# con-right-bot.net
KiCad netlist of a schematic drawn in Altium Designer
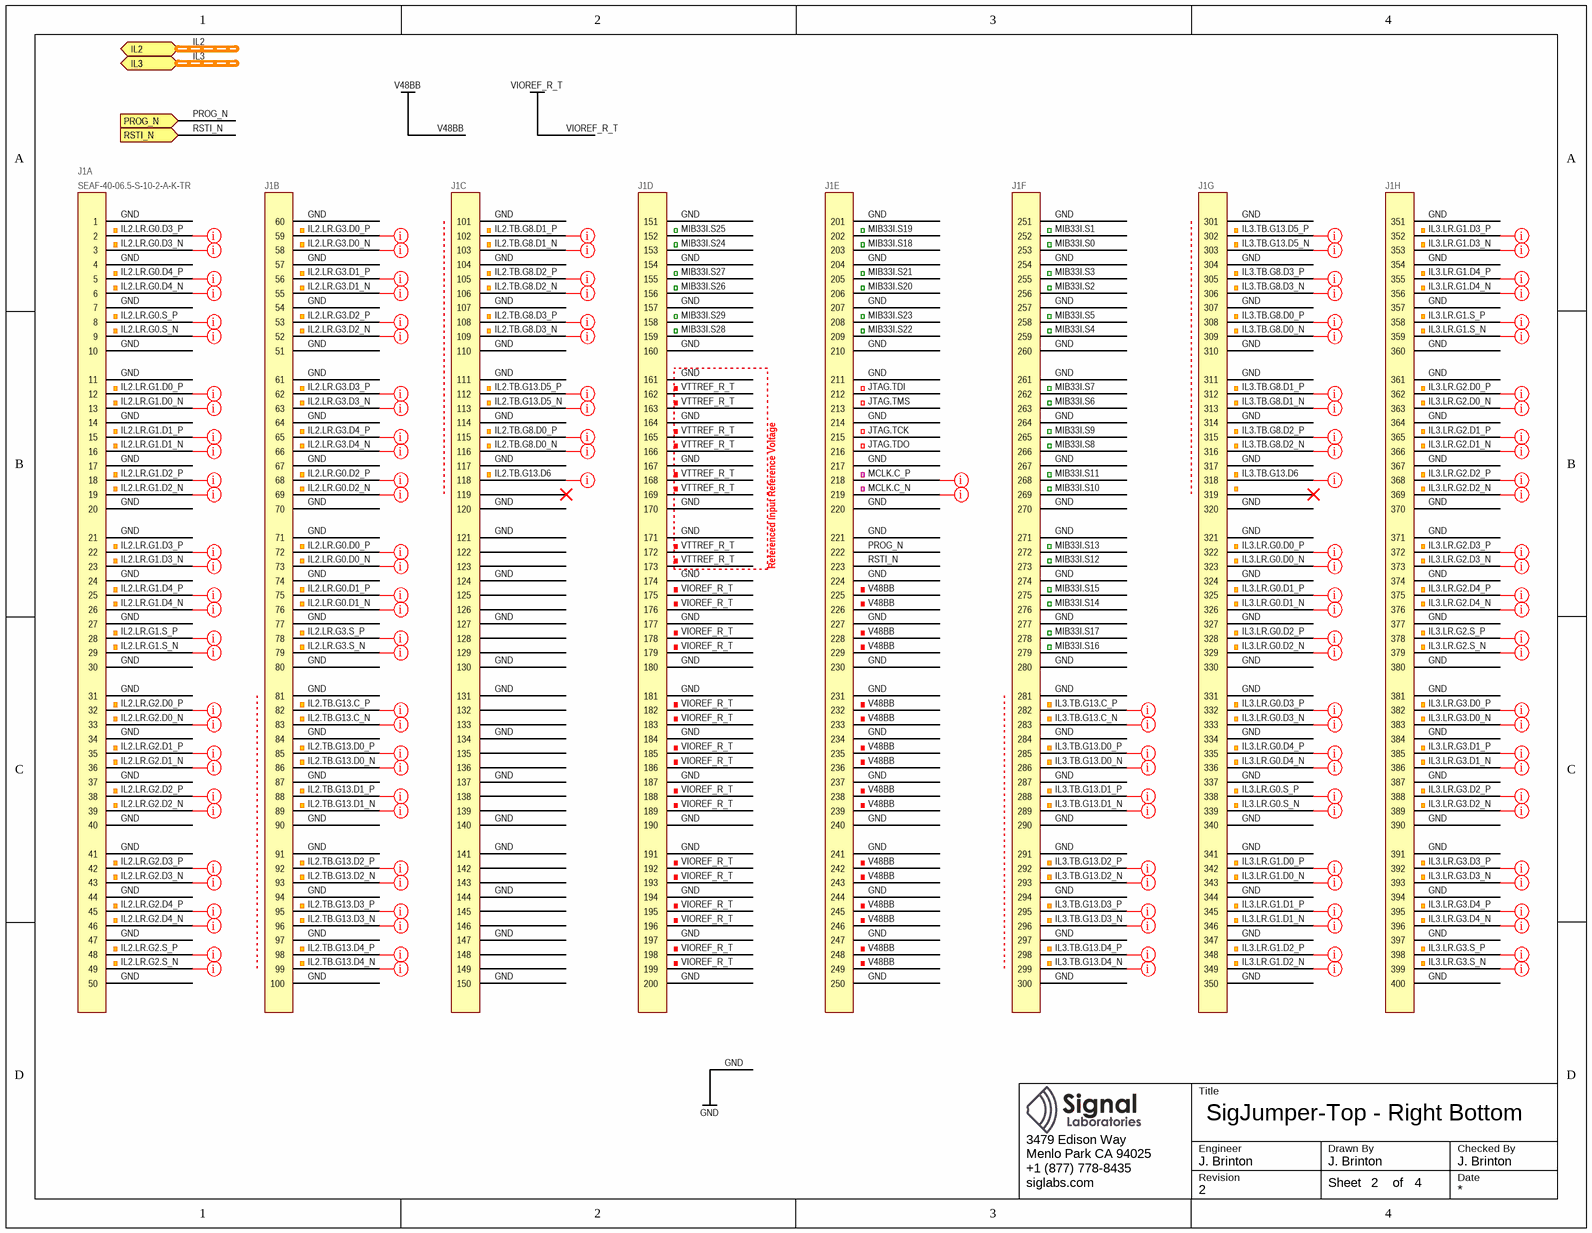
[diagram p0: con-right-bot.SchDoc]

(export (version "E")
  (design (tool "Eeschema 10.0.6"))
  (components
    (comp (ref "J1")
      (value "SEAF-40-06.5-S-10-2-A-K-TR")
      (footprint "samtec:SEAF-40-06.5-S-10-2-A-K-TR")
      (description "Terminal Array Assembly, Surface Mount, 0.050\" Pitch, 400 Pins")
      (fields (field (name "MANUFACTURER") "Samtec"))
      (libsource (lib "samtec") (part "SEAF-40-06.5-S-10-2-A-K-TR"))
    )
  )
  (nets
    (net (code "3") (name "/IL2.LR.G0.D0_N") (class "Default")
      (node (ref "J1") (pin "73") (pinfunction "73_73") (pintype "passive"))
    )
    (net (code "4") (name "/IL2.LR.G0.D0_P") (class "Default")
      (node (ref "J1") (pin "72") (pinfunction "72_72") (pintype "passive"))
    )
    (net (code "5") (name "/IL2.LR.G0.D1_N") (class "Default")
      (node (ref "J1") (pin "76") (pinfunction "76_76") (pintype "passive"))
    )
    (net (code "6") (name "/IL2.LR.G0.D1_P") (class "Default")
      (node (ref "J1") (pin "75") (pinfunction "75_75") (pintype "passive"))
    )
    (net (code "7") (name "/IL2.LR.G0.D2_N") (class "Default")
      (node (ref "J1") (pin "69") (pinfunction "69_69") (pintype "passive"))
    )
    (net (code "8") (name "/IL2.LR.G0.D2_P") (class "Default")
      (node (ref "J1") (pin "68") (pinfunction "68_68") (pintype "passive"))
    )
    (net (code "9") (name "/IL2.LR.G0.D3_N") (class "Default")
      (node (ref "J1") (pin "3") (pinfunction "3_3") (pintype "passive"))
    )
    (net (code "10") (name "/IL2.LR.G0.D3_P") (class "Default")
      (node (ref "J1") (pin "2") (pinfunction "2_2") (pintype "passive"))
    )
    (net (code "11") (name "/IL2.LR.G0.D4_N") (class "Default")
      (node (ref "J1") (pin "6") (pinfunction "6_6") (pintype "passive"))
    )
    (net (code "12") (name "/IL2.LR.G0.D4_P") (class "Default")
      (node (ref "J1") (pin "5") (pinfunction "5_5") (pintype "passive"))
    )
    (net (code "13") (name "/IL2.LR.G0.S_N") (class "Default")
      (node (ref "J1") (pin "9") (pinfunction "9_9") (pintype "passive"))
    )
    (net (code "14") (name "/IL2.LR.G0.S_P") (class "Default")
      (node (ref "J1") (pin "8") (pinfunction "8_8") (pintype "passive"))
    )
    (net (code "15") (name "/IL2.LR.G1.D0_N") (class "Default")
      (node (ref "J1") (pin "13") (pinfunction "13_13") (pintype "passive"))
    )
    (net (code "16") (name "/IL2.LR.G1.D0_P") (class "Default")
      (node (ref "J1") (pin "12") (pinfunction "12_12") (pintype "passive"))
    )
    (net (code "17") (name "/IL2.LR.G1.D1_N") (class "Default")
      (node (ref "J1") (pin "16") (pinfunction "16_16") (pintype "passive"))
    )
    (net (code "18") (name "/IL2.LR.G1.D1_P") (class "Default")
      (node (ref "J1") (pin "15") (pinfunction "15_15") (pintype "passive"))
    )
    (net (code "19") (name "/IL2.LR.G1.D2_N") (class "Default")
      (node (ref "J1") (pin "19") (pinfunction "19_19") (pintype "passive"))
    )
    (net (code "20") (name "/IL2.LR.G1.D2_P") (class "Default")
      (node (ref "J1") (pin "18") (pinfunction "18_18") (pintype "passive"))
    )
    (net (code "21") (name "/IL2.LR.G1.D3_N") (class "Default")
      (node (ref "J1") (pin "23") (pinfunction "23_23") (pintype "passive"))
    )
    (net (code "22") (name "/IL2.LR.G1.D3_P") (class "Default")
      (node (ref "J1") (pin "22") (pinfunction "22_22") (pintype "passive"))
    )
    (net (code "23") (name "/IL2.LR.G1.D4_N") (class "Default")
      (node (ref "J1") (pin "26") (pinfunction "26_26") (pintype "passive"))
    )
    (net (code "24") (name "/IL2.LR.G1.D4_P") (class "Default")
      (node (ref "J1") (pin "25") (pinfunction "25_25") (pintype "passive"))
    )
    (net (code "25") (name "/IL2.LR.G1.S_N") (class "Default")
      (node (ref "J1") (pin "29") (pinfunction "29_29") (pintype "passive"))
    )
    (net (code "26") (name "/IL2.LR.G1.S_P") (class "Default")
      (node (ref "J1") (pin "28") (pinfunction "28_28") (pintype "passive"))
    )
    (net (code "27") (name "/IL2.LR.G2.D0_N") (class "Default")
      (node (ref "J1") (pin "33") (pinfunction "33_33") (pintype "passive"))
    )
    (net (code "28") (name "/IL2.LR.G2.D0_P") (class "Default")
      (node (ref "J1") (pin "32") (pinfunction "32_32") (pintype "passive"))
    )
    (net (code "29") (name "/IL2.LR.G2.D1_N") (class "Default")
      (node (ref "J1") (pin "36") (pinfunction "36_36") (pintype "passive"))
    )
    (net (code "30") (name "/IL2.LR.G2.D1_P") (class "Default")
      (node (ref "J1") (pin "35") (pinfunction "35_35") (pintype "passive"))
    )
    (net (code "31") (name "/IL2.LR.G2.D2_N") (class "Default")
      (node (ref "J1") (pin "39") (pinfunction "39_39") (pintype "passive"))
    )
    (net (code "32") (name "/IL2.LR.G2.D2_P") (class "Default")
      (node (ref "J1") (pin "38") (pinfunction "38_38") (pintype "passive"))
    )
    (net (code "33") (name "/IL2.LR.G2.D3_N") (class "Default")
      (node (ref "J1") (pin "43") (pinfunction "43_43") (pintype "passive"))
    )
    (net (code "34") (name "/IL2.LR.G2.D3_P") (class "Default")
      (node (ref "J1") (pin "42") (pinfunction "42_42") (pintype "passive"))
    )
    (net (code "35") (name "/IL2.LR.G2.D4_N") (class "Default")
      (node (ref "J1") (pin "46") (pinfunction "46_46") (pintype "passive"))
    )
    (net (code "36") (name "/IL2.LR.G2.D4_P") (class "Default")
      (node (ref "J1") (pin "45") (pinfunction "45_45") (pintype "passive"))
    )
    (net (code "37") (name "/IL2.LR.G2.S_N") (class "Default")
      (node (ref "J1") (pin "49") (pinfunction "49_49") (pintype "passive"))
    )
    (net (code "38") (name "/IL2.LR.G2.S_P") (class "Default")
      (node (ref "J1") (pin "48") (pinfunction "48_48") (pintype "passive"))
    )
    (net (code "39") (name "/IL2.LR.G3.D0_N") (class "Default")
      (node (ref "J1") (pin "58") (pinfunction "58_58") (pintype "passive"))
    )
    (net (code "40") (name "/IL2.LR.G3.D0_P") (class "Default")
      (node (ref "J1") (pin "59") (pinfunction "59_59") (pintype "passive"))
    )
    (net (code "41") (name "/IL2.LR.G3.D1_N") (class "Default")
      (node (ref "J1") (pin "55") (pinfunction "55_55") (pintype "passive"))
    )
    (net (code "42") (name "/IL2.LR.G3.D1_P") (class "Default")
      (node (ref "J1") (pin "56") (pinfunction "56_56") (pintype "passive"))
    )
    (net (code "43") (name "/IL2.LR.G3.D2_N") (class "Default")
      (node (ref "J1") (pin "52") (pinfunction "52_52") (pintype "passive"))
    )
    (net (code "44") (name "/IL2.LR.G3.D2_P") (class "Default")
      (node (ref "J1") (pin "53") (pinfunction "53_53") (pintype "passive"))
    )
    (net (code "45") (name "/IL2.LR.G3.D3_N") (class "Default")
      (node (ref "J1") (pin "63") (pinfunction "63_63") (pintype "passive"))
    )
    (net (code "46") (name "/IL2.LR.G3.D3_P") (class "Default")
      (node (ref "J1") (pin "62") (pinfunction "62_62") (pintype "passive"))
    )
    (net (code "47") (name "/IL2.LR.G3.D4_N") (class "Default")
      (node (ref "J1") (pin "66") (pinfunction "66_66") (pintype "passive"))
    )
    (net (code "48") (name "/IL2.LR.G3.D4_P") (class "Default")
      (node (ref "J1") (pin "65") (pinfunction "65_65") (pintype "passive"))
    )
    (net (code "49") (name "/IL2.LR.G3.S_N") (class "Default")
      (node (ref "J1") (pin "79") (pinfunction "79_79") (pintype "passive"))
    )
    (net (code "50") (name "/IL2.LR.G3.S_P") (class "Default")
      (node (ref "J1") (pin "78") (pinfunction "78_78") (pintype "passive"))
    )
    (net (code "51") (name "/IL2.TB.G8.D0_N") (class "Default")
      (node (ref "J1") (pin "116") (pinfunction "116_116") (pintype "passive"))
    )
    (net (code "52") (name "/IL2.TB.G8.D0_P") (class "Default")
      (node (ref "J1") (pin "115") (pinfunction "115_115") (pintype "passive"))
    )
    (net (code "53") (name "/IL2.TB.G8.D1_N") (class "Default")
      (node (ref "J1") (pin "103") (pinfunction "103_103") (pintype "passive"))
    )
    (net (code "54") (name "/IL2.TB.G8.D1_P") (class "Default")
      (node (ref "J1") (pin "102") (pinfunction "102_102") (pintype "passive"))
    )
    (net (code "55") (name "/IL2.TB.G8.D2_N") (class "Default")
      (node (ref "J1") (pin "106") (pinfunction "106_106") (pintype "passive"))
    )
    (net (code "56") (name "/IL2.TB.G8.D2_P") (class "Default")
      (node (ref "J1") (pin "105") (pinfunction "105_105") (pintype "passive"))
    )
    (net (code "57") (name "/IL2.TB.G8.D3_N") (class "Default")
      (node (ref "J1") (pin "109") (pinfunction "109_109") (pintype "passive"))
    )
    (net (code "58") (name "/IL2.TB.G8.D3_P") (class "Default")
      (node (ref "J1") (pin "108") (pinfunction "108_108") (pintype "passive"))
    )
    (net (code "59") (name "/IL2.TB.G13.C_N") (class "Default")
      (node (ref "J1") (pin "83") (pinfunction "83_83") (pintype "passive"))
    )
    (net (code "60") (name "/IL2.TB.G13.C_P") (class "Default")
      (node (ref "J1") (pin "82") (pinfunction "82_82") (pintype "passive"))
    )
    (net (code "61") (name "/IL2.TB.G13.D0_N") (class "Default")
      (node (ref "J1") (pin "86") (pinfunction "86_86") (pintype "passive"))
    )
    (net (code "62") (name "/IL2.TB.G13.D0_P") (class "Default")
      (node (ref "J1") (pin "85") (pinfunction "85_85") (pintype "passive"))
    )
    (net (code "63") (name "/IL2.TB.G13.D1_N") (class "Default")
      (node (ref "J1") (pin "89") (pinfunction "89_89") (pintype "passive"))
    )
    (net (code "64") (name "/IL2.TB.G13.D1_P") (class "Default")
      (node (ref "J1") (pin "88") (pinfunction "88_88") (pintype "passive"))
    )
    (net (code "65") (name "/IL2.TB.G13.D2_N") (class "Default")
      (node (ref "J1") (pin "93") (pinfunction "93_93") (pintype "passive"))
    )
    (net (code "66") (name "/IL2.TB.G13.D2_P") (class "Default")
      (node (ref "J1") (pin "92") (pinfunction "92_92") (pintype "passive"))
    )
    (net (code "67") (name "/IL2.TB.G13.D3_N") (class "Default")
      (node (ref "J1") (pin "96") (pinfunction "96_96") (pintype "passive"))
    )
    (net (code "68") (name "/IL2.TB.G13.D3_P") (class "Default")
      (node (ref "J1") (pin "95") (pinfunction "95_95") (pintype "passive"))
    )
    (net (code "69") (name "/IL2.TB.G13.D4_N") (class "Default")
      (node (ref "J1") (pin "99") (pinfunction "99_99") (pintype "passive"))
    )
    (net (code "70") (name "/IL2.TB.G13.D4_P") (class "Default")
      (node (ref "J1") (pin "98") (pinfunction "98_98") (pintype "passive"))
    )
    (net (code "71") (name "/IL2.TB.G13.D5_N") (class "Default")
      (node (ref "J1") (pin "113") (pinfunction "113_113") (pintype "passive"))
    )
    (net (code "72") (name "/IL2.TB.G13.D5_P") (class "Default")
      (node (ref "J1") (pin "112") (pinfunction "112_112") (pintype "passive"))
    )
    (net (code "73") (name "/IL2.TB.G13.D6") (class "Default")
      (node (ref "J1") (pin "118") (pinfunction "118_118") (pintype "passive"))
    )
    (net (code "74") (name "/IL3.LR.G0.D0_N") (class "Default")
      (node (ref "J1") (pin "323") (pinfunction "323_323") (pintype "passive"))
    )
    (net (code "75") (name "/IL3.LR.G0.D0_P") (class "Default")
      (node (ref "J1") (pin "322") (pinfunction "322_322") (pintype "passive"))
    )
    (net (code "76") (name "/IL3.LR.G0.D1_N") (class "Default")
      (node (ref "J1") (pin "326") (pinfunction "326_326") (pintype "passive"))
    )
    (net (code "77") (name "/IL3.LR.G0.D1_P") (class "Default")
      (node (ref "J1") (pin "325") (pinfunction "325_325") (pintype "passive"))
    )
    (net (code "78") (name "/IL3.LR.G0.D2_N") (class "Default")
      (node (ref "J1") (pin "329") (pinfunction "329_329") (pintype "passive"))
    )
    (net (code "79") (name "/IL3.LR.G0.D2_P") (class "Default")
      (node (ref "J1") (pin "328") (pinfunction "328_328") (pintype "passive"))
    )
    (net (code "80") (name "/IL3.LR.G0.D3_N") (class "Default")
      (node (ref "J1") (pin "333") (pinfunction "333_333") (pintype "passive"))
    )
    (net (code "81") (name "/IL3.LR.G0.D3_P") (class "Default")
      (node (ref "J1") (pin "332") (pinfunction "332_332") (pintype "passive"))
    )
    (net (code "82") (name "/IL3.LR.G0.D4_N") (class "Default")
      (node (ref "J1") (pin "336") (pinfunction "336_336") (pintype "passive"))
    )
    (net (code "83") (name "/IL3.LR.G0.D4_P") (class "Default")
      (node (ref "J1") (pin "335") (pinfunction "335_335") (pintype "passive"))
    )
    (net (code "84") (name "/IL3.LR.G0.S_N") (class "Default")
      (node (ref "J1") (pin "339") (pinfunction "339_339") (pintype "passive"))
    )
    (net (code "85") (name "/IL3.LR.G0.S_P") (class "Default")
      (node (ref "J1") (pin "338") (pinfunction "338_338") (pintype "passive"))
    )
    (net (code "86") (name "/IL3.LR.G1.D0_N") (class "Default")
      (node (ref "J1") (pin "343") (pinfunction "343_343") (pintype "passive"))
    )
    (net (code "87") (name "/IL3.LR.G1.D0_P") (class "Default")
      (node (ref "J1") (pin "342") (pinfunction "342_342") (pintype "passive"))
    )
    (net (code "88") (name "/IL3.LR.G1.D1_N") (class "Default")
      (node (ref "J1") (pin "346") (pinfunction "346_346") (pintype "passive"))
    )
    (net (code "89") (name "/IL3.LR.G1.D1_P") (class "Default")
      (node (ref "J1") (pin "345") (pinfunction "345_345") (pintype "passive"))
    )
    (net (code "90") (name "/IL3.LR.G1.D2_N") (class "Default")
      (node (ref "J1") (pin "349") (pinfunction "349_349") (pintype "passive"))
    )
    (net (code "91") (name "/IL3.LR.G1.D2_P") (class "Default")
      (node (ref "J1") (pin "348") (pinfunction "348_348") (pintype "passive"))
    )
    (net (code "92") (name "/IL3.LR.G1.D3_N") (class "Default")
      (node (ref "J1") (pin "353") (pinfunction "353_353") (pintype "passive"))
    )
    (net (code "93") (name "/IL3.LR.G1.D3_P") (class "Default")
      (node (ref "J1") (pin "352") (pinfunction "352_352") (pintype "passive"))
    )
    (net (code "94") (name "/IL3.LR.G1.D4_N") (class "Default")
      (node (ref "J1") (pin "356") (pinfunction "356_356") (pintype "passive"))
    )
    (net (code "95") (name "/IL3.LR.G1.D4_P") (class "Default")
      (node (ref "J1") (pin "355") (pinfunction "355_355") (pintype "passive"))
    )
    (net (code "96") (name "/IL3.LR.G1.S_N") (class "Default")
      (node (ref "J1") (pin "359") (pinfunction "359_359") (pintype "passive"))
    )
    (net (code "97") (name "/IL3.LR.G1.S_P") (class "Default")
      (node (ref "J1") (pin "358") (pinfunction "358_358") (pintype "passive"))
    )
    (net (code "98") (name "/IL3.LR.G2.D0_N") (class "Default")
      (node (ref "J1") (pin "363") (pinfunction "363_363") (pintype "passive"))
    )
    (net (code "99") (name "/IL3.LR.G2.D0_P") (class "Default")
      (node (ref "J1") (pin "362") (pinfunction "362_362") (pintype "passive"))
    )
    (net (code "100") (name "/IL3.LR.G2.D1_N") (class "Default")
      (node (ref "J1") (pin "366") (pinfunction "366_366") (pintype "passive"))
    )
    (net (code "101") (name "/IL3.LR.G2.D1_P") (class "Default")
      (node (ref "J1") (pin "365") (pinfunction "365_365") (pintype "passive"))
    )
    (net (code "102") (name "/IL3.LR.G2.D2_N") (class "Default")
      (node (ref "J1") (pin "369") (pinfunction "369_369") (pintype "passive"))
    )
    (net (code "103") (name "/IL3.LR.G2.D2_P") (class "Default")
      (node (ref "J1") (pin "368") (pinfunction "368_368") (pintype "passive"))
    )
    (net (code "104") (name "/IL3.LR.G2.D3_N") (class "Default")
      (node (ref "J1") (pin "373") (pinfunction "373_373") (pintype "passive"))
    )
    (net (code "105") (name "/IL3.LR.G2.D3_P") (class "Default")
      (node (ref "J1") (pin "372") (pinfunction "372_372") (pintype "passive"))
    )
    (net (code "106") (name "/IL3.LR.G2.D4_N") (class "Default")
      (node (ref "J1") (pin "376") (pinfunction "376_376") (pintype "passive"))
    )
    (net (code "107") (name "/IL3.LR.G2.D4_P") (class "Default")
      (node (ref "J1") (pin "375") (pinfunction "375_375") (pintype "passive"))
    )
    (net (code "108") (name "/IL3.LR.G2.S_N") (class "Default")
      (node (ref "J1") (pin "379") (pinfunction "379_379") (pintype "passive"))
    )
    (net (code "109") (name "/IL3.LR.G2.S_P") (class "Default")
      (node (ref "J1") (pin "378") (pinfunction "378_378") (pintype "passive"))
    )
    (net (code "110") (name "/IL3.LR.G3.D0_N") (class "Default")
      (node (ref "J1") (pin "383") (pinfunction "383_383") (pintype "passive"))
    )
    (net (code "111") (name "/IL3.LR.G3.D0_P") (class "Default")
      (node (ref "J1") (pin "382") (pinfunction "382_382") (pintype "passive"))
    )
    (net (code "112") (name "/IL3.LR.G3.D1_N") (class "Default")
      (node (ref "J1") (pin "386") (pinfunction "386_386") (pintype "passive"))
    )
    (net (code "113") (name "/IL3.LR.G3.D1_P") (class "Default")
      (node (ref "J1") (pin "385") (pinfunction "385_385") (pintype "passive"))
    )
    (net (code "114") (name "/IL3.LR.G3.D2_N") (class "Default")
      (node (ref "J1") (pin "389") (pinfunction "389_389") (pintype "passive"))
    )
    (net (code "115") (name "/IL3.LR.G3.D2_P") (class "Default")
      (node (ref "J1") (pin "388") (pinfunction "388_388") (pintype "passive"))
    )
    (net (code "116") (name "/IL3.LR.G3.D3_N") (class "Default")
      (node (ref "J1") (pin "393") (pinfunction "393_393") (pintype "passive"))
    )
    (net (code "117") (name "/IL3.LR.G3.D3_P") (class "Default")
      (node (ref "J1") (pin "392") (pinfunction "392_392") (pintype "passive"))
    )
    (net (code "118") (name "/IL3.LR.G3.D4_N") (class "Default")
      (node (ref "J1") (pin "396") (pinfunction "396_396") (pintype "passive"))
    )
    (net (code "119") (name "/IL3.LR.G3.D4_P") (class "Default")
      (node (ref "J1") (pin "395") (pinfunction "395_395") (pintype "passive"))
    )
    (net (code "120") (name "/IL3.LR.G3.S_N") (class "Default")
      (node (ref "J1") (pin "399") (pinfunction "399_399") (pintype "passive"))
    )
    (net (code "121") (name "/IL3.LR.G3.S_P") (class "Default")
      (node (ref "J1") (pin "398") (pinfunction "398_398") (pintype "passive"))
    )
    (net (code "122") (name "/IL3.TB.G8.D0_N") (class "Default")
      (node (ref "J1") (pin "309") (pinfunction "309_309") (pintype "passive"))
    )
    (net (code "123") (name "/IL3.TB.G8.D0_P") (class "Default")
      (node (ref "J1") (pin "308") (pinfunction "308_308") (pintype "passive"))
    )
    (net (code "124") (name "/IL3.TB.G8.D1_N") (class "Default")
      (node (ref "J1") (pin "313") (pinfunction "313_313") (pintype "passive"))
    )
    (net (code "125") (name "/IL3.TB.G8.D1_P") (class "Default")
      (node (ref "J1") (pin "312") (pinfunction "312_312") (pintype "passive"))
    )
    (net (code "126") (name "/IL3.TB.G8.D2_N") (class "Default")
      (node (ref "J1") (pin "316") (pinfunction "316_316") (pintype "passive"))
    )
    (net (code "127") (name "/IL3.TB.G8.D2_P") (class "Default")
      (node (ref "J1") (pin "315") (pinfunction "315_315") (pintype "passive"))
    )
    (net (code "128") (name "/IL3.TB.G8.D3_N") (class "Default")
      (node (ref "J1") (pin "306") (pinfunction "306_306") (pintype "passive"))
    )
    (net (code "129") (name "/IL3.TB.G8.D3_P") (class "Default")
      (node (ref "J1") (pin "305") (pinfunction "305_305") (pintype "passive"))
    )
    (net (code "130") (name "/IL3.TB.G13.C_N") (class "Default")
      (node (ref "J1") (pin "283") (pinfunction "283_283") (pintype "passive"))
    )
    (net (code "131") (name "/IL3.TB.G13.C_P") (class "Default")
      (node (ref "J1") (pin "282") (pinfunction "282_282") (pintype "passive"))
    )
    (net (code "132") (name "/IL3.TB.G13.D0_N") (class "Default")
      (node (ref "J1") (pin "286") (pinfunction "286_286") (pintype "passive"))
    )
    (net (code "133") (name "/IL3.TB.G13.D0_P") (class "Default")
      (node (ref "J1") (pin "285") (pinfunction "285_285") (pintype "passive"))
    )
    (net (code "134") (name "/IL3.TB.G13.D1_N") (class "Default")
      (node (ref "J1") (pin "289") (pinfunction "289_289") (pintype "passive"))
    )
    (net (code "135") (name "/IL3.TB.G13.D1_P") (class "Default")
      (node (ref "J1") (pin "288") (pinfunction "288_288") (pintype "passive"))
    )
    (net (code "136") (name "/IL3.TB.G13.D2_N") (class "Default")
      (node (ref "J1") (pin "293") (pinfunction "293_293") (pintype "passive"))
    )
    (net (code "137") (name "/IL3.TB.G13.D2_P") (class "Default")
      (node (ref "J1") (pin "292") (pinfunction "292_292") (pintype "passive"))
    )
    (net (code "138") (name "/IL3.TB.G13.D3_N") (class "Default")
      (node (ref "J1") (pin "296") (pinfunction "296_296") (pintype "passive"))
    )
    (net (code "139") (name "/IL3.TB.G13.D3_P") (class "Default")
      (node (ref "J1") (pin "295") (pinfunction "295_295") (pintype "passive"))
    )
    (net (code "140") (name "/IL3.TB.G13.D4_N") (class "Default")
      (node (ref "J1") (pin "299") (pinfunction "299_299") (pintype "passive"))
    )
    (net (code "141") (name "/IL3.TB.G13.D4_P") (class "Default")
      (node (ref "J1") (pin "298") (pinfunction "298_298") (pintype "passive"))
    )
    (net (code "142") (name "/IL3.TB.G13.D5_N") (class "Default")
      (node (ref "J1") (pin "303") (pinfunction "303_303") (pintype "passive"))
    )
    (net (code "143") (name "/IL3.TB.G13.D5_P") (class "Default")
      (node (ref "J1") (pin "302") (pinfunction "302_302") (pintype "passive"))
    )
    (net (code "144") (name "/IL3.TB.G13.D6") (class "Default")
      (node (ref "J1") (pin "318") (pinfunction "318_318") (pintype "passive"))
    )
    (net (code "145") (name "/JTAG.TCK") (class "Default")
      (node (ref "J1") (pin "215") (pinfunction "215_215") (pintype "passive"))
    )
    (net (code "146") (name "/JTAG.TDI") (class "Default")
      (node (ref "J1") (pin "212") (pinfunction "212_212") (pintype "passive"))
    )
    (net (code "147") (name "/JTAG.TDO") (class "Default")
      (node (ref "J1") (pin "216") (pinfunction "216_216") (pintype "passive"))
    )
    (net (code "148") (name "/JTAG.TMS") (class "Default")
      (node (ref "J1") (pin "213") (pinfunction "213_213") (pintype "passive"))
    )
    (net (code "149") (name "/MCLK.C_N") (class "Default")
      (node (ref "J1") (pin "219") (pinfunction "219_219") (pintype "passive"))
    )
    (net (code "150") (name "/MCLK.C_P") (class "Default")
      (node (ref "J1") (pin "218") (pinfunction "218_218") (pintype "passive"))
    )
    (net (code "151") (name "/MIB33I.S0") (class "Default")
      (node (ref "J1") (pin "253") (pinfunction "253_253") (pintype "passive"))
    )
    (net (code "152") (name "/MIB33I.S1") (class "Default")
      (node (ref "J1") (pin "252") (pinfunction "252_252") (pintype "passive"))
    )
    (net (code "153") (name "/MIB33I.S2") (class "Default")
      (node (ref "J1") (pin "256") (pinfunction "256_256") (pintype "passive"))
    )
    (net (code "154") (name "/MIB33I.S3") (class "Default")
      (node (ref "J1") (pin "255") (pinfunction "255_255") (pintype "passive"))
    )
    (net (code "155") (name "/MIB33I.S4") (class "Default")
      (node (ref "J1") (pin "259") (pinfunction "259_259") (pintype "passive"))
    )
    (net (code "156") (name "/MIB33I.S5") (class "Default")
      (node (ref "J1") (pin "258") (pinfunction "258_258") (pintype "passive"))
    )
    (net (code "157") (name "/MIB33I.S6") (class "Default")
      (node (ref "J1") (pin "263") (pinfunction "263_263") (pintype "passive"))
    )
    (net (code "158") (name "/MIB33I.S7") (class "Default")
      (node (ref "J1") (pin "262") (pinfunction "262_262") (pintype "passive"))
    )
    (net (code "159") (name "/MIB33I.S8") (class "Default")
      (node (ref "J1") (pin "266") (pinfunction "266_266") (pintype "passive"))
    )
    (net (code "160") (name "/MIB33I.S9") (class "Default")
      (node (ref "J1") (pin "265") (pinfunction "265_265") (pintype "passive"))
    )
    (net (code "161") (name "/MIB33I.S10") (class "Default")
      (node (ref "J1") (pin "269") (pinfunction "269_269") (pintype "passive"))
    )
    (net (code "162") (name "/MIB33I.S11") (class "Default")
      (node (ref "J1") (pin "268") (pinfunction "268_268") (pintype "passive"))
    )
    (net (code "163") (name "/MIB33I.S12") (class "Default")
      (node (ref "J1") (pin "273") (pinfunction "273_273") (pintype "passive"))
    )
    (net (code "164") (name "/MIB33I.S13") (class "Default")
      (node (ref "J1") (pin "272") (pinfunction "272_272") (pintype "passive"))
    )
    (net (code "165") (name "/MIB33I.S14") (class "Default")
      (node (ref "J1") (pin "276") (pinfunction "276_276") (pintype "passive"))
    )
    (net (code "166") (name "/MIB33I.S15") (class "Default")
      (node (ref "J1") (pin "275") (pinfunction "275_275") (pintype "passive"))
    )
    (net (code "167") (name "/MIB33I.S16") (class "Default")
      (node (ref "J1") (pin "279") (pinfunction "279_279") (pintype "passive"))
    )
    (net (code "168") (name "/MIB33I.S17") (class "Default")
      (node (ref "J1") (pin "278") (pinfunction "278_278") (pintype "passive"))
    )
    (net (code "169") (name "/MIB33I.S18") (class "Default")
      (node (ref "J1") (pin "203") (pinfunction "203_203") (pintype "passive"))
    )
    (net (code "170") (name "/MIB33I.S19") (class "Default")
      (node (ref "J1") (pin "202") (pinfunction "202_202") (pintype "passive"))
    )
    (net (code "171") (name "/MIB33I.S20") (class "Default")
      (node (ref "J1") (pin "206") (pinfunction "206_206") (pintype "passive"))
    )
    (net (code "172") (name "/MIB33I.S21") (class "Default")
      (node (ref "J1") (pin "205") (pinfunction "205_205") (pintype "passive"))
    )
    (net (code "173") (name "/MIB33I.S22") (class "Default")
      (node (ref "J1") (pin "209") (pinfunction "209_209") (pintype "passive"))
    )
    (net (code "174") (name "/MIB33I.S23") (class "Default")
      (node (ref "J1") (pin "208") (pinfunction "208_208") (pintype "passive"))
    )
    (net (code "175") (name "/MIB33I.S24") (class "Default")
      (node (ref "J1") (pin "153") (pinfunction "153_153") (pintype "passive"))
    )
    (net (code "176") (name "/MIB33I.S25") (class "Default")
      (node (ref "J1") (pin "152") (pinfunction "152_152") (pintype "passive"))
    )
    (net (code "177") (name "/MIB33I.S26") (class "Default")
      (node (ref "J1") (pin "156") (pinfunction "156_156") (pintype "passive"))
    )
    (net (code "178") (name "/MIB33I.S27") (class "Default")
      (node (ref "J1") (pin "155") (pinfunction "155_155") (pintype "passive"))
    )
    (net (code "179") (name "/MIB33I.S28") (class "Default")
      (node (ref "J1") (pin "159") (pinfunction "159_159") (pintype "passive"))
    )
    (net (code "180") (name "/MIB33I.S29") (class "Default")
      (node (ref "J1") (pin "158") (pinfunction "158_158") (pintype "passive"))
    )
    (net (code "181") (name "/PROG_N") (class "Default")
      (node (ref "J1") (pin "222") (pinfunction "222_222") (pintype "passive"))
    )
    (net (code "182") (name "/RSTI_N") (class "Default")
      (node (ref "J1") (pin "223") (pinfunction "223_223") (pintype "passive"))
    )
    (net (code "183") (name "/VTTREF_R_T") (class "Default")
      (node (ref "J1") (pin "162") (pinfunction "162_162") (pintype "passive"))
      (node (ref "J1") (pin "163") (pinfunction "163_163") (pintype "passive"))
      (node (ref "J1") (pin "165") (pinfunction "165_165") (pintype "passive"))
      (node (ref "J1") (pin "166") (pinfunction "166_166") (pintype "passive"))
      (node (ref "J1") (pin "168") (pinfunction "168_168") (pintype "passive"))
      (node (ref "J1") (pin "169") (pinfunction "169_169") (pintype "passive"))
      (node (ref "J1") (pin "172") (pinfunction "172_172") (pintype "passive"))
      (node (ref "J1") (pin "173") (pinfunction "173_173") (pintype "passive"))
    )
    (net (code "186") (name "GND") (class "Default")
      (node (ref "J1") (pin "1") (pinfunction "1_1") (pintype "passive"))
      (node (ref "J1") (pin "10") (pinfunction "10_10") (pintype "passive"))
      (node (ref "J1") (pin "100") (pinfunction "100_100") (pintype "passive"))
      (node (ref "J1") (pin "101") (pinfunction "101_101") (pintype "passive"))
      (node (ref "J1") (pin "104") (pinfunction "104_104") (pintype "passive"))
      (node (ref "J1") (pin "107") (pinfunction "107_107") (pintype "passive"))
      (node (ref "J1") (pin "11") (pinfunction "11_11") (pintype "passive"))
      (node (ref "J1") (pin "110") (pinfunction "110_110") (pintype "passive"))
      (node (ref "J1") (pin "111") (pinfunction "111_111") (pintype "passive"))
      (node (ref "J1") (pin "114") (pinfunction "114_114") (pintype "passive"))
      (node (ref "J1") (pin "117") (pinfunction "117_117") (pintype "passive"))
      (node (ref "J1") (pin "120") (pinfunction "120_120") (pintype "passive"))
      (node (ref "J1") (pin "121") (pinfunction "121_121") (pintype "passive"))
      (node (ref "J1") (pin "124") (pinfunction "124_124") (pintype "passive"))
      (node (ref "J1") (pin "127") (pinfunction "127_127") (pintype "passive"))
      (node (ref "J1") (pin "130") (pinfunction "130_130") (pintype "passive"))
      (node (ref "J1") (pin "131") (pinfunction "131_131") (pintype "passive"))
      (node (ref "J1") (pin "134") (pinfunction "134_134") (pintype "passive"))
      (node (ref "J1") (pin "137") (pinfunction "137_137") (pintype "passive"))
      (node (ref "J1") (pin "14") (pinfunction "14_14") (pintype "passive"))
      (node (ref "J1") (pin "140") (pinfunction "140_140") (pintype "passive"))
      (node (ref "J1") (pin "141") (pinfunction "141_141") (pintype "passive"))
      (node (ref "J1") (pin "144") (pinfunction "144_144") (pintype "passive"))
      (node (ref "J1") (pin "147") (pinfunction "147_147") (pintype "passive"))
      (node (ref "J1") (pin "150") (pinfunction "150_150") (pintype "passive"))
      (node (ref "J1") (pin "151") (pinfunction "151_151") (pintype "passive"))
      (node (ref "J1") (pin "154") (pinfunction "154_154") (pintype "passive"))
      (node (ref "J1") (pin "157") (pinfunction "157_157") (pintype "passive"))
      (node (ref "J1") (pin "160") (pinfunction "160_160") (pintype "passive"))
      (node (ref "J1") (pin "161") (pinfunction "161_161") (pintype "passive"))
      (node (ref "J1") (pin "164") (pinfunction "164_164") (pintype "passive"))
      (node (ref "J1") (pin "167") (pinfunction "167_167") (pintype "passive"))
      (node (ref "J1") (pin "17") (pinfunction "17_17") (pintype "passive"))
      (node (ref "J1") (pin "170") (pinfunction "170_170") (pintype "passive"))
      (node (ref "J1") (pin "171") (pinfunction "171_171") (pintype "passive"))
      (node (ref "J1") (pin "174") (pinfunction "174_174") (pintype "passive"))
      (node (ref "J1") (pin "177") (pinfunction "177_177") (pintype "passive"))
      (node (ref "J1") (pin "180") (pinfunction "180_180") (pintype "passive"))
      (node (ref "J1") (pin "181") (pinfunction "181_181") (pintype "passive"))
      (node (ref "J1") (pin "184") (pinfunction "184_184") (pintype "passive"))
      (node (ref "J1") (pin "187") (pinfunction "187_187") (pintype "passive"))
      (node (ref "J1") (pin "190") (pinfunction "190_190") (pintype "passive"))
      (node (ref "J1") (pin "191") (pinfunction "191_191") (pintype "passive"))
      (node (ref "J1") (pin "194") (pinfunction "194_194") (pintype "passive"))
      (node (ref "J1") (pin "197") (pinfunction "197_197") (pintype "passive"))
      (node (ref "J1") (pin "20") (pinfunction "20_20") (pintype "passive"))
      (node (ref "J1") (pin "200") (pinfunction "200_200") (pintype "passive"))
      (node (ref "J1") (pin "201") (pinfunction "201_201") (pintype "passive"))
      (node (ref "J1") (pin "204") (pinfunction "204_204") (pintype "passive"))
      (node (ref "J1") (pin "207") (pinfunction "207_207") (pintype "passive"))
      (node (ref "J1") (pin "21") (pinfunction "21_21") (pintype "passive"))
      (node (ref "J1") (pin "210") (pinfunction "210_210") (pintype "passive"))
      (node (ref "J1") (pin "211") (pinfunction "211_211") (pintype "passive"))
      (node (ref "J1") (pin "214") (pinfunction "214_214") (pintype "passive"))
      (node (ref "J1") (pin "217") (pinfunction "217_217") (pintype "passive"))
      (node (ref "J1") (pin "220") (pinfunction "220_220") (pintype "passive"))
      (node (ref "J1") (pin "221") (pinfunction "221_221") (pintype "passive"))
      (node (ref "J1") (pin "224") (pinfunction "224_224") (pintype "passive"))
      (node (ref "J1") (pin "227") (pinfunction "227_227") (pintype "passive"))
      (node (ref "J1") (pin "230") (pinfunction "230_230") (pintype "passive"))
      (node (ref "J1") (pin "231") (pinfunction "231_231") (pintype "passive"))
      (node (ref "J1") (pin "234") (pinfunction "234_234") (pintype "passive"))
      (node (ref "J1") (pin "237") (pinfunction "237_237") (pintype "passive"))
      (node (ref "J1") (pin "24") (pinfunction "24_24") (pintype "passive"))
      (node (ref "J1") (pin "240") (pinfunction "240_240") (pintype "passive"))
      (node (ref "J1") (pin "241") (pinfunction "241_241") (pintype "passive"))
      (node (ref "J1") (pin "244") (pinfunction "244_244") (pintype "passive"))
      (node (ref "J1") (pin "247") (pinfunction "247_247") (pintype "passive"))
      (node (ref "J1") (pin "250") (pinfunction "250_250") (pintype "passive"))
      (node (ref "J1") (pin "251") (pinfunction "251_251") (pintype "passive"))
      (node (ref "J1") (pin "254") (pinfunction "254_254") (pintype "passive"))
      (node (ref "J1") (pin "257") (pinfunction "257_257") (pintype "passive"))
      (node (ref "J1") (pin "260") (pinfunction "260_260") (pintype "passive"))
      (node (ref "J1") (pin "261") (pinfunction "261_261") (pintype "passive"))
      (node (ref "J1") (pin "264") (pinfunction "264_264") (pintype "passive"))
      (node (ref "J1") (pin "267") (pinfunction "267_267") (pintype "passive"))
      (node (ref "J1") (pin "27") (pinfunction "27_27") (pintype "passive"))
      (node (ref "J1") (pin "270") (pinfunction "270_270") (pintype "passive"))
      (node (ref "J1") (pin "271") (pinfunction "271_271") (pintype "passive"))
      (node (ref "J1") (pin "274") (pinfunction "274_274") (pintype "passive"))
      (node (ref "J1") (pin "277") (pinfunction "277_277") (pintype "passive"))
      (node (ref "J1") (pin "280") (pinfunction "280_280") (pintype "passive"))
      (node (ref "J1") (pin "281") (pinfunction "281_281") (pintype "passive"))
      (node (ref "J1") (pin "284") (pinfunction "284_284") (pintype "passive"))
      (node (ref "J1") (pin "287") (pinfunction "287_287") (pintype "passive"))
      (node (ref "J1") (pin "290") (pinfunction "290_290") (pintype "passive"))
      (node (ref "J1") (pin "291") (pinfunction "291_291") (pintype "passive"))
      (node (ref "J1") (pin "294") (pinfunction "294_294") (pintype "passive"))
      (node (ref "J1") (pin "297") (pinfunction "297_297") (pintype "passive"))
      (node (ref "J1") (pin "30") (pinfunction "30_30") (pintype "passive"))
      (node (ref "J1") (pin "300") (pinfunction "300_300") (pintype "passive"))
      (node (ref "J1") (pin "301") (pinfunction "301_301") (pintype "passive"))
      (node (ref "J1") (pin "304") (pinfunction "304_304") (pintype "passive"))
      (node (ref "J1") (pin "307") (pinfunction "307_307") (pintype "passive"))
      (node (ref "J1") (pin "31") (pinfunction "31_31") (pintype "passive"))
      (node (ref "J1") (pin "310") (pinfunction "310_310") (pintype "passive"))
      (node (ref "J1") (pin "311") (pinfunction "311_311") (pintype "passive"))
      (node (ref "J1") (pin "314") (pinfunction "314_314") (pintype "passive"))
      (node (ref "J1") (pin "317") (pinfunction "317_317") (pintype "passive"))
      (node (ref "J1") (pin "320") (pinfunction "320_320") (pintype "passive"))
      (node (ref "J1") (pin "321") (pinfunction "321_321") (pintype "passive"))
      (node (ref "J1") (pin "324") (pinfunction "324_324") (pintype "passive"))
      (node (ref "J1") (pin "327") (pinfunction "327_327") (pintype "passive"))
      (node (ref "J1") (pin "330") (pinfunction "330_330") (pintype "passive"))
      (node (ref "J1") (pin "331") (pinfunction "331_331") (pintype "passive"))
      (node (ref "J1") (pin "334") (pinfunction "334_334") (pintype "passive"))
      (node (ref "J1") (pin "337") (pinfunction "337_337") (pintype "passive"))
      (node (ref "J1") (pin "34") (pinfunction "34_34") (pintype "passive"))
      (node (ref "J1") (pin "340") (pinfunction "340_340") (pintype "passive"))
      (node (ref "J1") (pin "341") (pinfunction "341_341") (pintype "passive"))
      (node (ref "J1") (pin "344") (pinfunction "344_344") (pintype "passive"))
      (node (ref "J1") (pin "347") (pinfunction "347_347") (pintype "passive"))
      (node (ref "J1") (pin "350") (pinfunction "350_350") (pintype "passive"))
      (node (ref "J1") (pin "351") (pinfunction "351_351") (pintype "passive"))
      (node (ref "J1") (pin "354") (pinfunction "354_354") (pintype "passive"))
      (node (ref "J1") (pin "357") (pinfunction "357_357") (pintype "passive"))
      (node (ref "J1") (pin "360") (pinfunction "360_360") (pintype "passive"))
      (node (ref "J1") (pin "361") (pinfunction "361_361") (pintype "passive"))
      (node (ref "J1") (pin "364") (pinfunction "364_364") (pintype "passive"))
      (node (ref "J1") (pin "367") (pinfunction "367_367") (pintype "passive"))
      (node (ref "J1") (pin "37") (pinfunction "37_37") (pintype "passive"))
      (node (ref "J1") (pin "370") (pinfunction "370_370") (pintype "passive"))
      (node (ref "J1") (pin "371") (pinfunction "371_371") (pintype "passive"))
      (node (ref "J1") (pin "374") (pinfunction "374_374") (pintype "passive"))
      (node (ref "J1") (pin "377") (pinfunction "377_377") (pintype "passive"))
      (node (ref "J1") (pin "380") (pinfunction "380_380") (pintype "passive"))
      (node (ref "J1") (pin "381") (pinfunction "381_381") (pintype "passive"))
      (node (ref "J1") (pin "384") (pinfunction "384_384") (pintype "passive"))
      (node (ref "J1") (pin "387") (pinfunction "387_387") (pintype "passive"))
      (node (ref "J1") (pin "390") (pinfunction "390_390") (pintype "passive"))
      (node (ref "J1") (pin "391") (pinfunction "391_391") (pintype "passive"))
      (node (ref "J1") (pin "394") (pinfunction "394_394") (pintype "passive"))
      (node (ref "J1") (pin "397") (pinfunction "397_397") (pintype "passive"))
      (node (ref "J1") (pin "4") (pinfunction "4_4") (pintype "passive"))
      (node (ref "J1") (pin "40") (pinfunction "40_40") (pintype "passive"))
      (node (ref "J1") (pin "400") (pinfunction "400_400") (pintype "passive"))
      (node (ref "J1") (pin "41") (pinfunction "41_41") (pintype "passive"))
      (node (ref "J1") (pin "44") (pinfunction "44_44") (pintype "passive"))
      (node (ref "J1") (pin "47") (pinfunction "47_47") (pintype "passive"))
      (node (ref "J1") (pin "50") (pinfunction "50_50") (pintype "passive"))
      (node (ref "J1") (pin "51") (pinfunction "51_51") (pintype "passive"))
      (node (ref "J1") (pin "54") (pinfunction "54_54") (pintype "passive"))
      (node (ref "J1") (pin "57") (pinfunction "57_57") (pintype "passive"))
      (node (ref "J1") (pin "60") (pinfunction "60_60") (pintype "passive"))
      (node (ref "J1") (pin "61") (pinfunction "61_61") (pintype "passive"))
      (node (ref "J1") (pin "64") (pinfunction "64_64") (pintype "passive"))
      (node (ref "J1") (pin "67") (pinfunction "67_67") (pintype "passive"))
      (node (ref "J1") (pin "7") (pinfunction "7_7") (pintype "passive"))
      (node (ref "J1") (pin "70") (pinfunction "70_70") (pintype "passive"))
      (node (ref "J1") (pin "71") (pinfunction "71_71") (pintype "passive"))
      (node (ref "J1") (pin "74") (pinfunction "74_74") (pintype "passive"))
      (node (ref "J1") (pin "77") (pinfunction "77_77") (pintype "passive"))
      (node (ref "J1") (pin "80") (pinfunction "80_80") (pintype "passive"))
      (node (ref "J1") (pin "81") (pinfunction "81_81") (pintype "passive"))
      (node (ref "J1") (pin "84") (pinfunction "84_84") (pintype "passive"))
      (node (ref "J1") (pin "87") (pinfunction "87_87") (pintype "passive"))
      (node (ref "J1") (pin "90") (pinfunction "90_90") (pintype "passive"))
      (node (ref "J1") (pin "91") (pinfunction "91_91") (pintype "passive"))
      (node (ref "J1") (pin "94") (pinfunction "94_94") (pintype "passive"))
      (node (ref "J1") (pin "97") (pinfunction "97_97") (pintype "passive"))
    )
    (net (code "187") (name "V48BB") (class "Default")
      (node (ref "J1") (pin "225") (pinfunction "225_225") (pintype "passive"))
      (node (ref "J1") (pin "226") (pinfunction "226_226") (pintype "passive"))
      (node (ref "J1") (pin "228") (pinfunction "228_228") (pintype "passive"))
      (node (ref "J1") (pin "229") (pinfunction "229_229") (pintype "passive"))
      (node (ref "J1") (pin "232") (pinfunction "232_232") (pintype "passive"))
      (node (ref "J1") (pin "233") (pinfunction "233_233") (pintype "passive"))
      (node (ref "J1") (pin "235") (pinfunction "235_235") (pintype "passive"))
      (node (ref "J1") (pin "236") (pinfunction "236_236") (pintype "passive"))
      (node (ref "J1") (pin "238") (pinfunction "238_238") (pintype "passive"))
      (node (ref "J1") (pin "239") (pinfunction "239_239") (pintype "passive"))
      (node (ref "J1") (pin "242") (pinfunction "242_242") (pintype "passive"))
      (node (ref "J1") (pin "243") (pinfunction "243_243") (pintype "passive"))
      (node (ref "J1") (pin "245") (pinfunction "245_245") (pintype "passive"))
      (node (ref "J1") (pin "246") (pinfunction "246_246") (pintype "passive"))
      (node (ref "J1") (pin "248") (pinfunction "248_248") (pintype "passive"))
      (node (ref "J1") (pin "249") (pinfunction "249_249") (pintype "passive"))
    )
    (net (code "188") (name "VIOREF_R_T") (class "Default")
      (node (ref "J1") (pin "175") (pinfunction "175_175") (pintype "passive"))
      (node (ref "J1") (pin "176") (pinfunction "176_176") (pintype "passive"))
      (node (ref "J1") (pin "178") (pinfunction "178_178") (pintype "passive"))
      (node (ref "J1") (pin "179") (pinfunction "179_179") (pintype "passive"))
      (node (ref "J1") (pin "182") (pinfunction "182_182") (pintype "passive"))
      (node (ref "J1") (pin "183") (pinfunction "183_183") (pintype "passive"))
      (node (ref "J1") (pin "185") (pinfunction "185_185") (pintype "passive"))
      (node (ref "J1") (pin "186") (pinfunction "186_186") (pintype "passive"))
      (node (ref "J1") (pin "188") (pinfunction "188_188") (pintype "passive"))
      (node (ref "J1") (pin "189") (pinfunction "189_189") (pintype "passive"))
      (node (ref "J1") (pin "192") (pinfunction "192_192") (pintype "passive"))
      (node (ref "J1") (pin "193") (pinfunction "193_193") (pintype "passive"))
      (node (ref "J1") (pin "195") (pinfunction "195_195") (pintype "passive"))
      (node (ref "J1") (pin "196") (pinfunction "196_196") (pintype "passive"))
      (node (ref "J1") (pin "198") (pinfunction "198_198") (pintype "passive"))
      (node (ref "J1") (pin "199") (pinfunction "199_199") (pintype "passive"))
    )
    (net (code "189") (name "unconnected-(J1-Pad119)") (class "Default")
      (node (ref "J1") (pin "119") (pinfunction "119_119") (pintype "passive+no_connect"))
    )
    (net (code "190") (name "unconnected-(J1-Pad122)") (class "Default")
      (node (ref "J1") (pin "122") (pinfunction "122_122") (pintype "passive"))
    )
    (net (code "191") (name "unconnected-(J1-Pad123)") (class "Default")
      (node (ref "J1") (pin "123") (pinfunction "123_123") (pintype "passive"))
    )
    (net (code "192") (name "unconnected-(J1-Pad125)") (class "Default")
      (node (ref "J1") (pin "125") (pinfunction "125_125") (pintype "passive"))
    )
    (net (code "193") (name "unconnected-(J1-Pad126)") (class "Default")
      (node (ref "J1") (pin "126") (pinfunction "126_126") (pintype "passive"))
    )
    (net (code "194") (name "unconnected-(J1-Pad128)") (class "Default")
      (node (ref "J1") (pin "128") (pinfunction "128_128") (pintype "passive"))
    )
    (net (code "195") (name "unconnected-(J1-Pad129)") (class "Default")
      (node (ref "J1") (pin "129") (pinfunction "129_129") (pintype "passive"))
    )
    (net (code "196") (name "unconnected-(J1-Pad132)") (class "Default")
      (node (ref "J1") (pin "132") (pinfunction "132_132") (pintype "passive"))
    )
    (net (code "197") (name "unconnected-(J1-Pad133)") (class "Default")
      (node (ref "J1") (pin "133") (pinfunction "133_133") (pintype "passive"))
    )
    (net (code "198") (name "unconnected-(J1-Pad135)") (class "Default")
      (node (ref "J1") (pin "135") (pinfunction "135_135") (pintype "passive"))
    )
    (net (code "199") (name "unconnected-(J1-Pad136)") (class "Default")
      (node (ref "J1") (pin "136") (pinfunction "136_136") (pintype "passive"))
    )
    (net (code "200") (name "unconnected-(J1-Pad138)") (class "Default")
      (node (ref "J1") (pin "138") (pinfunction "138_138") (pintype "passive"))
    )
    (net (code "201") (name "unconnected-(J1-Pad139)") (class "Default")
      (node (ref "J1") (pin "139") (pinfunction "139_139") (pintype "passive"))
    )
    (net (code "202") (name "unconnected-(J1-Pad142)") (class "Default")
      (node (ref "J1") (pin "142") (pinfunction "142_142") (pintype "passive"))
    )
    (net (code "203") (name "unconnected-(J1-Pad143)") (class "Default")
      (node (ref "J1") (pin "143") (pinfunction "143_143") (pintype "passive"))
    )
    (net (code "204") (name "unconnected-(J1-Pad145)") (class "Default")
      (node (ref "J1") (pin "145") (pinfunction "145_145") (pintype "passive"))
    )
    (net (code "205") (name "unconnected-(J1-Pad146)") (class "Default")
      (node (ref "J1") (pin "146") (pinfunction "146_146") (pintype "passive"))
    )
    (net (code "206") (name "unconnected-(J1-Pad148)") (class "Default")
      (node (ref "J1") (pin "148") (pinfunction "148_148") (pintype "passive"))
    )
    (net (code "207") (name "unconnected-(J1-Pad149)") (class "Default")
      (node (ref "J1") (pin "149") (pinfunction "149_149") (pintype "passive"))
    )
    (net (code "208") (name "unconnected-(J1-Pad319)") (class "Default")
      (node (ref "J1") (pin "319") (pinfunction "319_319") (pintype "passive+no_connect"))
    )
  )
)
